# Adafruit_Feather_RP2040.net
KiCad netlist of a schematic drawn in EAGLE
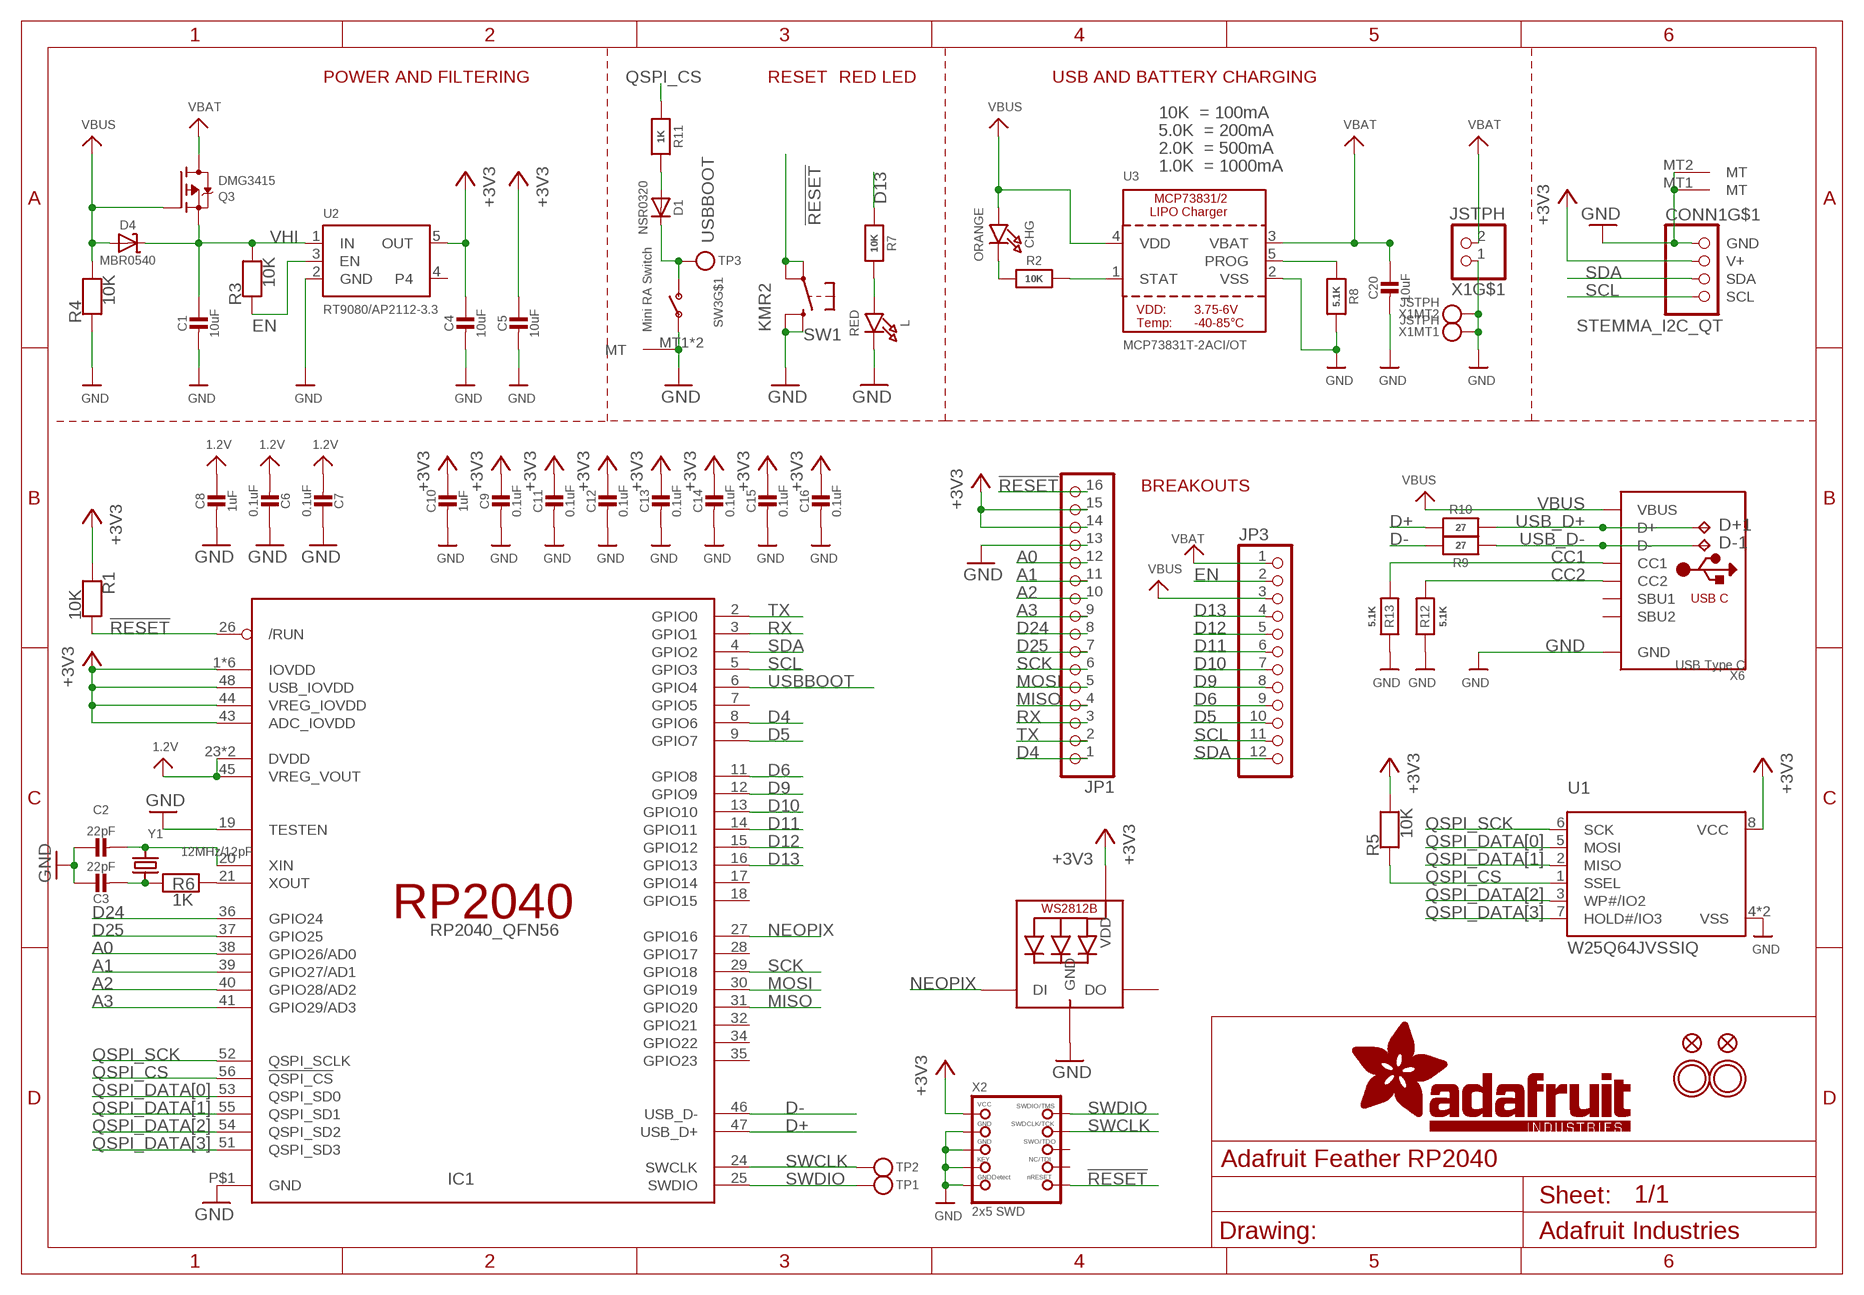
[diagram p0: schematic, sheet 1]

(export (version "E")
  (design (tool "Eeschema 10.0.6"))
  (components
    (comp (ref "C1")
      (value "10uF")
      (footprint "eagle-import:0805-NO")
      (libsource (lib "eagle-import") (part "CAP_CERAMIC0805-NOOUTLINE"))
    )
    (comp (ref "C2")
      (value "22pF")
      (footprint "eagle-import:0603-NO")
      (libsource (lib "eagle-import") (part "CAP_CERAMIC0603_NO"))
    )
    (comp (ref "C3")
      (value "22pF")
      (footprint "eagle-import:0603-NO")
      (libsource (lib "eagle-import") (part "CAP_CERAMIC0603_NO"))
    )
    (comp (ref "C4")
      (value "10uF")
      (footprint "eagle-import:0805-NO")
      (fields (field (name "REV") "D"))
      (libsource (lib "eagle-import") (part "CAP_CERAMIC0805-NOOUTLINE"))
    )
    (comp (ref "C5")
      (value "10uF")
      (footprint "eagle-import:0805-NO")
      (libsource (lib "eagle-import") (part "CAP_CERAMIC0805-NOOUTLINE"))
    )
    (comp (ref "C6")
      (value "0.1uF")
      (footprint "eagle-import:0603-NO")
      (libsource (lib "eagle-import") (part "CAP_CERAMIC0603_NO"))
    )
    (comp (ref "C7")
      (value "0.1uF")
      (footprint "eagle-import:0603-NO")
      (libsource (lib "eagle-import") (part "CAP_CERAMIC0603_NO"))
    )
    (comp (ref "C8")
      (value "1uF")
      (footprint "eagle-import:0603-NO")
      (libsource (lib "eagle-import") (part "CAP_CERAMIC0603_NO"))
    )
    (comp (ref "C9")
      (value "0.1uF")
      (footprint "eagle-import:0603-NO")
      (libsource (lib "eagle-import") (part "CAP_CERAMIC0603_NO"))
    )
    (comp (ref "C10")
      (value "1uF")
      (footprint "eagle-import:0603-NO")
      (libsource (lib "eagle-import") (part "CAP_CERAMIC0603_NO"))
    )
    (comp (ref "C11")
      (value "0.1uF")
      (footprint "eagle-import:0603-NO")
      (libsource (lib "eagle-import") (part "CAP_CERAMIC0603_NO"))
    )
    (comp (ref "C12")
      (value "0.1uF")
      (footprint "eagle-import:0603-NO")
      (libsource (lib "eagle-import") (part "CAP_CERAMIC0603_NO"))
    )
    (comp (ref "C13")
      (value "0.1uF")
      (footprint "eagle-import:0603-NO")
      (libsource (lib "eagle-import") (part "CAP_CERAMIC0603_NO"))
    )
    (comp (ref "C14")
      (value "0.1uF")
      (footprint "eagle-import:0603-NO")
      (libsource (lib "eagle-import") (part "CAP_CERAMIC0603_NO"))
    )
    (comp (ref "C15")
      (value "0.1uF")
      (footprint "eagle-import:0603-NO")
      (libsource (lib "eagle-import") (part "CAP_CERAMIC0603_NO"))
    )
    (comp (ref "C16")
      (value "0.1uF")
      (footprint "eagle-import:0603-NO")
      (libsource (lib "eagle-import") (part "CAP_CERAMIC0603_NO"))
    )
    (comp (ref "C20")
      (value "10uF")
      (footprint "eagle-import:0805-NO")
      (libsource (lib "eagle-import") (part "CAP_CERAMIC0805-NOOUTLINE"))
    )
    (comp (ref "CHG")
      (value "ORANGE")
      (footprint "eagle-import:CHIPLED_0603_NOOUTLINE")
      (libsource (lib "eagle-import") (part "LED0603_NOOUTLINE"))
    )
    (comp (ref "CONN1")
      (value "STEMMA_I2C_QT")
      (footprint "eagle-import:JST_SH4")
      (libsource (lib "eagle-import") (part "STEMMA_I2C_QT"))
    )
    (comp (ref "D+1")
      (value "TPB1,27")
      (footprint "eagle-import:B1,27")
      (libsource (lib "eagle-import") (part "TPB1,27"))
    )
    (comp (ref "D-1")
      (value "TPB1,27")
      (footprint "eagle-import:B1,27")
      (libsource (lib "eagle-import") (part "TPB1,27"))
    )
    (comp (ref "D1")
      (value "NSR0320")
      (footprint "eagle-import:SOD-323_MINI")
      (libsource (lib "eagle-import") (part "DIODE_SOD323MINI"))
    )
    (comp (ref "D4")
      (value "MBR0540")
      (footprint "eagle-import:SOD-123")
      (libsource (lib "eagle-import") (part "DIODE-SCHOTTKYSOD-123"))
    )
    (comp (ref "IC1")
      (value "RP2040_QFN56")
      (footprint "eagle-import:QFN56_7MM_REDUCEDEPAD")
      (libsource (lib "eagle-import") (part "RP2040_QFN56"))
    )
    (comp (ref "JP1")
      (value "HEADER-1X16ROUND")
      (footprint "eagle-import:1X16_ROUND")
      (libsource (lib "eagle-import") (part "HEADER-1X16ROUND"))
    )
    (comp (ref "JP3")
      (value "HEADER-1X12")
      (footprint "eagle-import:1X12_ROUND")
      (libsource (lib "eagle-import") (part "HEADER-1X12"))
    )
    (comp (ref "L")
      (value "RED")
      (footprint "eagle-import:CHIPLED_0603_NOOUTLINE")
      (libsource (lib "eagle-import") (part "LED0603_NOOUTLINE"))
    )
    (comp (ref "LED1")
      (value "WS2812B3535")
      (footprint "eagle-import:LED3535")
      (libsource (lib "eagle-import") (part "WS2812B3535"))
    )
    (comp (ref "Q3")
      (value "DMG3415")
      (footprint "eagle-import:SOT23-R")
      (libsource (lib "eagle-import") (part "MOSFET-P"))
    )
    (comp (ref "R1")
      (value "10K")
      (footprint "eagle-import:0603-NO")
      (libsource (lib "eagle-import") (part "RESISTOR_0603_NOOUT"))
    )
    (comp (ref "R2")
      (value "10K")
      (footprint "eagle-import:0603-NO")
      (libsource (lib "eagle-import") (part "RESISTOR_0603_NOOUT"))
    )
    (comp (ref "R3")
      (value "10K")
      (footprint "eagle-import:0603-NO")
      (libsource (lib "eagle-import") (part "RESISTOR_0603_NOOUT"))
    )
    (comp (ref "R4")
      (value "10K")
      (footprint "eagle-import:0603-NO")
      (libsource (lib "eagle-import") (part "RESISTOR_0603_NOOUT"))
    )
    (comp (ref "R5")
      (value "10K")
      (footprint "eagle-import:0603-NO")
      (libsource (lib "eagle-import") (part "RESISTOR_0603_NOOUT"))
    )
    (comp (ref "R6")
      (value "1K")
      (footprint "eagle-import:0603-NO")
      (libsource (lib "eagle-import") (part "RESISTOR_0603_NOOUT"))
    )
    (comp (ref "R7")
      (value "10K")
      (footprint "eagle-import:0603-NO")
      (libsource (lib "eagle-import") (part "RESISTOR_0603_NOOUT"))
    )
    (comp (ref "R8")
      (value "5.1K")
      (footprint "eagle-import:0603-NO")
      (libsource (lib "eagle-import") (part "RESISTOR_0603_NOOUT"))
    )
    (comp (ref "R9")
      (value "27")
      (footprint "eagle-import:0603-NO")
      (libsource (lib "eagle-import") (part "RESISTOR_0603_NOOUT"))
    )
    (comp (ref "R10")
      (value "27")
      (footprint "eagle-import:0603-NO")
      (libsource (lib "eagle-import") (part "RESISTOR_0603_NOOUT"))
    )
    (comp (ref "R11")
      (value "1K")
      (footprint "eagle-import:0603-NO")
      (libsource (lib "eagle-import") (part "RESISTOR_0603_NOOUT"))
    )
    (comp (ref "R12")
      (value "5.1K")
      (footprint "eagle-import:0603-NO")
      (libsource (lib "eagle-import") (part "RESISTOR_0603_NOOUT"))
    )
    (comp (ref "R13")
      (value "5.1K")
      (footprint "eagle-import:0603-NO")
      (libsource (lib "eagle-import") (part "RESISTOR_0603_NOOUT"))
    )
    (comp (ref "SW1")
      (value "KMR2")
      (footprint "eagle-import:BTN_KMR2_4.6X2.8")
      (libsource (lib "eagle-import") (part "SWITCH_TACT_SMT4.6X2.8"))
    )
    (comp (ref "SW3")
      (value "Mini RA Switch")
      (footprint "eagle-import:SPST_TACTILE_RA_2_4_3.5MM")
      (libsource (lib "eagle-import") (part "SWITCH_SPST_MNT_243.5"))
    )
    (comp (ref "TP1")
      (value "TESTPOINTROUND1.5MMNO")
      (footprint "eagle-import:TESTPOINT_ROUND_1.5MM_NO")
      (libsource (lib "eagle-import") (part "TESTPOINTROUND1.5MMNO"))
    )
    (comp (ref "TP2")
      (value "TESTPOINTROUND1.5MMNO")
      (footprint "eagle-import:TESTPOINT_ROUND_1.5MM_NO")
      (libsource (lib "eagle-import") (part "TESTPOINTROUND1.5MMNO"))
    )
    (comp (ref "TP3")
      (value "TESTPOINTROUND1.5MMNO")
      (footprint "eagle-import:TESTPOINT_ROUND_1.5MM_NO")
      (libsource (lib "eagle-import") (part "TESTPOINTROUND1.5MMNO"))
    )
    (comp (ref "U$31")
      (value "MOUNTINGHOLE2.5")
      (footprint "eagle-import:MOUNTINGHOLE_2.5_PLATED")
      (libsource (lib "eagle-import") (part "MOUNTINGHOLE2.5"))
    )
    (comp (ref "U$32")
      (value "MOUNTINGHOLE2.5")
      (footprint "eagle-import:MOUNTINGHOLE_2.5_PLATED")
      (libsource (lib "eagle-import") (part "MOUNTINGHOLE2.5"))
    )
    (comp (ref "U$34")
      (value "FIDUCIAL_1MM")
      (footprint "eagle-import:FIDUCIAL_1MM")
      (libsource (lib "eagle-import") (part "FIDUCIAL_1MM"))
    )
    (comp (ref "U$35")
      (value "FIDUCIAL_1MM")
      (footprint "eagle-import:FIDUCIAL_1MM")
      (libsource (lib "eagle-import") (part "FIDUCIAL_1MM"))
    )
    (comp (ref "U1")
      (value "W25Q64JVSSIQ")
      (footprint "eagle-import:USON8_4X4")
      (libsource (lib "eagle-import") (part "SPIFLASH_8PIN_4X4"))
    )
    (comp (ref "U2")
      (value "RT9080/AP2112-3.3")
      (footprint "eagle-import:SOT23-5")
      (fields (field (name "JLC_ROTATION") "0"))
      (libsource (lib "eagle-import") (part "VREG_SOT23-5"))
    )
    (comp (ref "U3")
      (value "MCP73831T-2ACI/OT")
      (footprint "eagle-import:SOT23-5")
      (libsource (lib "eagle-import") (part "MCP73831/2"))
    )
    (comp (ref "X1")
      (value "JSTPH")
      (footprint "eagle-import:JSTPH2_BATT")
      (libsource (lib "eagle-import") (part "CON_JST_PH_2PIN_MT_BATT"))
    )
    (comp (ref "X2")
      (value "2x5 SWD")
      (footprint "eagle-import:2X05_1.27MM_BOX_NOCREAM")
      (libsource (lib "eagle-import") (part "JTAG-CORTEX_NOCREAM"))
    )
    (comp (ref "X6")
      (value "USB Type C")
      (footprint "eagle-import:USB_C_CUSB31-CFM2AX-01-X")
      (libsource (lib "eagle-import") (part "USB_C"))
    )
    (comp (ref "Y1")
      (value "12MHz/12pF")
      (footprint "eagle-import:CRYSTAL_2.5X2")
      (libsource (lib "eagle-import") (part "CRYSTAL2.5X2.0"))
    )
  )
  (nets
    (net (code "1") (name "+3V3") (class "Default")
      (node (ref "C10") (pin "1") (pinfunction "1_1") (pintype "passive"))
      (node (ref "C11") (pin "1") (pinfunction "1_1") (pintype "passive"))
      (node (ref "C12") (pin "1") (pinfunction "1_1") (pintype "passive"))
      (node (ref "C13") (pin "1") (pinfunction "1_1") (pintype "passive"))
      (node (ref "C14") (pin "1") (pinfunction "1_1") (pintype "passive"))
      (node (ref "C15") (pin "1") (pinfunction "1_1") (pintype "passive"))
      (node (ref "C16") (pin "1") (pinfunction "1_1") (pintype "passive"))
      (node (ref "C4") (pin "1") (pinfunction "1_1") (pintype "passive"))
      (node (ref "C5") (pin "1") (pinfunction "1_1") (pintype "passive"))
      (node (ref "C9") (pin "1") (pinfunction "1_1") (pintype "passive"))
      (node (ref "CONN1") (pin "2") (pinfunction "V+_2") (pintype "passive"))
      (node (ref "IC1") (pin "1") (pinfunction "IOVDD_1") (pintype "power_in"))
      (node (ref "IC1") (pin "10") (pinfunction "IOVDD_10") (pintype "power_in"))
      (node (ref "IC1") (pin "22") (pinfunction "IOVDD_22") (pintype "power_in"))
      (node (ref "IC1") (pin "33") (pinfunction "IOVDD_33") (pintype "power_in"))
      (node (ref "IC1") (pin "42") (pinfunction "IOVDD_42") (pintype "power_in"))
      (node (ref "IC1") (pin "43") (pinfunction "ADC_IOVDD_43") (pintype "power_in"))
      (node (ref "IC1") (pin "44") (pinfunction "VREG_IOVDD_44") (pintype "power_in"))
      (node (ref "IC1") (pin "48") (pinfunction "USB_IOVDD_48") (pintype "power_in"))
      (node (ref "IC1") (pin "49") (pinfunction "IOVDD_49") (pintype "power_in"))
      (node (ref "JP1") (pin "14") (pinfunction "14_14") (pintype "passive"))
      (node (ref "JP1") (pin "15") (pinfunction "15_15") (pintype "passive"))
      (node (ref "LED1") (pin "2") (pinfunction "VDD_2") (pintype "power_in"))
      (node (ref "R1") (pin "1") (pinfunction "1_1") (pintype "passive"))
      (node (ref "R5") (pin "2") (pinfunction "2_2") (pintype "passive"))
      (node (ref "U1") (pin "8") (pinfunction "VCC_8") (pintype "bidirectional"))
      (node (ref "U2") (pin "5") (pinfunction "OUT_5") (pintype "power_in"))
      (node (ref "X2") (pin "1") (pinfunction "VCC_1") (pintype "power_in"))
    )
    (net (code "2") (name "/A0") (class "Default")
      (node (ref "IC1") (pin "38") (pinfunction "GPIO26/AD0_38") (pintype "bidirectional"))
      (node (ref "JP1") (pin "12") (pinfunction "12_12") (pintype "passive"))
    )
    (net (code "3") (name "/A1") (class "Default")
      (node (ref "IC1") (pin "39") (pinfunction "GPIO27/AD1_39") (pintype "bidirectional"))
      (node (ref "JP1") (pin "11") (pinfunction "11_11") (pintype "passive"))
    )
    (net (code "4") (name "/A2") (class "Default")
      (node (ref "IC1") (pin "40") (pinfunction "GPIO28/AD2_40") (pintype "bidirectional"))
      (node (ref "JP1") (pin "10") (pinfunction "10_10") (pintype "passive"))
    )
    (net (code "5") (name "/A3") (class "Default")
      (node (ref "IC1") (pin "41") (pinfunction "GPIO29/AD3_41") (pintype "bidirectional"))
      (node (ref "JP1") (pin "9") (pinfunction "9_9") (pintype "passive"))
    )
    (net (code "6") (name "/CC1") (class "Default")
      (node (ref "R13") (pin "2") (pinfunction "2_2") (pintype "passive"))
      (node (ref "X6") (pin "A5") (pinfunction "CC1_A5") (pintype "bidirectional"))
    )
    (net (code "7") (name "/CC2") (class "Default")
      (node (ref "R12") (pin "2") (pinfunction "2_2") (pintype "passive"))
      (node (ref "X6") (pin "B5") (pinfunction "CC2_B5") (pintype "bidirectional"))
    )
    (net (code "8") (name "/D+") (class "Default")
      (node (ref "IC1") (pin "47") (pinfunction "USB_D+_47") (pintype "bidirectional"))
      (node (ref "R10") (pin "2") (pinfunction "2_2") (pintype "passive"))
    )
    (net (code "9") (name "/D-") (class "Default")
      (node (ref "IC1") (pin "46") (pinfunction "USB_D-_46") (pintype "bidirectional"))
      (node (ref "R9") (pin "2") (pinfunction "2_2") (pintype "passive"))
    )
    (net (code "10") (name "/D4") (class "Default")
      (node (ref "IC1") (pin "8") (pinfunction "GPIO6_8") (pintype "bidirectional"))
      (node (ref "JP1") (pin "1") (pinfunction "1_1") (pintype "passive"))
    )
    (net (code "11") (name "/D5") (class "Default")
      (node (ref "IC1") (pin "9") (pinfunction "GPIO7_9") (pintype "bidirectional"))
      (node (ref "JP3") (pin "10") (pinfunction "10_10") (pintype "passive"))
    )
    (net (code "12") (name "/D6") (class "Default")
      (node (ref "IC1") (pin "11") (pinfunction "GPIO8_11") (pintype "bidirectional"))
      (node (ref "JP3") (pin "9") (pinfunction "9_9") (pintype "passive"))
    )
    (net (code "13") (name "/D9") (class "Default")
      (node (ref "IC1") (pin "12") (pinfunction "GPIO9_12") (pintype "bidirectional"))
      (node (ref "JP3") (pin "8") (pinfunction "8_8") (pintype "passive"))
    )
    (net (code "14") (name "/D10") (class "Default")
      (node (ref "IC1") (pin "13") (pinfunction "GPIO10_13") (pintype "bidirectional"))
      (node (ref "JP3") (pin "7") (pinfunction "7_7") (pintype "passive"))
    )
    (net (code "15") (name "/D11") (class "Default")
      (node (ref "IC1") (pin "14") (pinfunction "GPIO11_14") (pintype "bidirectional"))
      (node (ref "JP3") (pin "6") (pinfunction "6_6") (pintype "passive"))
    )
    (net (code "16") (name "/D12") (class "Default")
      (node (ref "IC1") (pin "15") (pinfunction "GPIO12_15") (pintype "bidirectional"))
      (node (ref "JP3") (pin "5") (pinfunction "5_5") (pintype "passive"))
    )
    (net (code "17") (name "/D13") (class "Default")
      (node (ref "IC1") (pin "16") (pinfunction "GPIO13_16") (pintype "bidirectional"))
      (node (ref "JP3") (pin "4") (pinfunction "4_4") (pintype "passive"))
      (node (ref "R7") (pin "1") (pinfunction "1_1") (pintype "passive"))
    )
    (net (code "18") (name "/D24") (class "Default")
      (node (ref "IC1") (pin "36") (pinfunction "GPIO24_36") (pintype "bidirectional"))
      (node (ref "JP1") (pin "8") (pinfunction "8_8") (pintype "passive"))
    )
    (net (code "19") (name "/D25") (class "Default")
      (node (ref "IC1") (pin "37") (pinfunction "GPIO25_37") (pintype "bidirectional"))
      (node (ref "JP1") (pin "7") (pinfunction "7_7") (pintype "passive"))
    )
    (net (code "20") (name "/EN") (class "Default")
      (node (ref "JP3") (pin "2") (pinfunction "2_2") (pintype "passive"))
      (node (ref "R3") (pin "1") (pinfunction "1_1") (pintype "passive"))
      (node (ref "U2") (pin "3") (pinfunction "EN_3") (pintype "input"))
    )
    (net (code "21") (name "/MISO") (class "Default")
      (node (ref "IC1") (pin "31") (pinfunction "GPIO20_31") (pintype "bidirectional"))
      (node (ref "JP1") (pin "4") (pinfunction "4_4") (pintype "passive"))
    )
    (net (code "22") (name "/MOSI") (class "Default")
      (node (ref "IC1") (pin "30") (pinfunction "GPIO19_30") (pintype "bidirectional"))
      (node (ref "JP1") (pin "5") (pinfunction "5_5") (pintype "passive"))
    )
    (net (code "23") (name "/NEOPIX") (class "Default")
      (node (ref "IC1") (pin "27") (pinfunction "GPIO16_27") (pintype "bidirectional"))
      (node (ref "LED1") (pin "1") (pinfunction "DI_1") (pintype "input"))
    )
    (net (code "24") (name "/QSPI_CS") (class "Default")
      (node (ref "IC1") (pin "56") (pinfunction "~{QSPI_CS}_56") (pintype "bidirectional"))
      (node (ref "R11") (pin "1") (pinfunction "1_1") (pintype "passive"))
      (node (ref "R5") (pin "1") (pinfunction "1_1") (pintype "passive"))
      (node (ref "U1") (pin "1") (pinfunction "SSEL_1") (pintype "bidirectional"))
    )
    (net (code "25") (name "/QSPI_DATA[0]") (class "Default")
      (node (ref "IC1") (pin "53") (pinfunction "QSPI_SD0_53") (pintype "bidirectional"))
      (node (ref "U1") (pin "5") (pinfunction "MOSI_5") (pintype "bidirectional"))
    )
    (net (code "26") (name "/QSPI_DATA[1]") (class "Default")
      (node (ref "IC1") (pin "55") (pinfunction "QSPI_SD1_55") (pintype "bidirectional"))
      (node (ref "U1") (pin "2") (pinfunction "MISO_2") (pintype "bidirectional"))
    )
    (net (code "27") (name "/QSPI_DATA[2]") (class "Default")
      (node (ref "IC1") (pin "54") (pinfunction "QSPI_SD2_54") (pintype "bidirectional"))
      (node (ref "U1") (pin "3") (pinfunction "WP#/IO2_3") (pintype "bidirectional"))
    )
    (net (code "28") (name "/QSPI_DATA[3]") (class "Default")
      (node (ref "IC1") (pin "51") (pinfunction "QSPI_SD3_51") (pintype "bidirectional"))
      (node (ref "U1") (pin "7") (pinfunction "HOLD#/IO3_7") (pintype "bidirectional"))
    )
    (net (code "29") (name "/QSPI_SCK") (class "Default")
      (node (ref "IC1") (pin "52") (pinfunction "QSPI_SCLK_52") (pintype "bidirectional"))
      (node (ref "U1") (pin "6") (pinfunction "SCK_6") (pintype "bidirectional"))
    )
    (net (code "30") (name "/RX") (class "Default")
      (node (ref "IC1") (pin "3") (pinfunction "GPIO1_3") (pintype "bidirectional"))
      (node (ref "JP1") (pin "3") (pinfunction "3_3") (pintype "passive"))
    )
    (net (code "31") (name "/SCK") (class "Default")
      (node (ref "IC1") (pin "29") (pinfunction "GPIO18_29") (pintype "bidirectional"))
      (node (ref "JP1") (pin "6") (pinfunction "6_6") (pintype "passive"))
    )
    (net (code "32") (name "/SCL") (class "Default")
      (node (ref "CONN1") (pin "4") (pinfunction "SCL_4") (pintype "passive"))
      (node (ref "IC1") (pin "5") (pinfunction "GPIO3_5") (pintype "bidirectional"))
      (node (ref "JP3") (pin "11") (pinfunction "11_11") (pintype "passive"))
    )
    (net (code "33") (name "/SDA") (class "Default")
      (node (ref "CONN1") (pin "3") (pinfunction "SDA_3") (pintype "passive"))
      (node (ref "IC1") (pin "4") (pinfunction "GPIO2_4") (pintype "bidirectional"))
      (node (ref "JP3") (pin "12") (pinfunction "12_12") (pintype "passive"))
    )
    (net (code "34") (name "/SWCLK") (class "Default")
      (node (ref "IC1") (pin "24") (pinfunction "SWCLK_24") (pintype "bidirectional"))
      (node (ref "TP2") (pin "P$1") (pinfunction "P$1_P$1") (pintype "bidirectional"))
      (node (ref "X2") (pin "4") (pinfunction "SWDCLK_4") (pintype "bidirectional"))
    )
    (net (code "35") (name "/SWDIO") (class "Default")
      (node (ref "IC1") (pin "25") (pinfunction "SWDIO_25") (pintype "bidirectional"))
      (node (ref "TP1") (pin "P$1") (pinfunction "P$1_P$1") (pintype "bidirectional"))
      (node (ref "X2") (pin "2") (pinfunction "SWDIO_2") (pintype "bidirectional"))
    )
    (net (code "36") (name "/TX") (class "Default")
      (node (ref "IC1") (pin "2") (pinfunction "GPIO0_2") (pintype "bidirectional"))
      (node (ref "JP1") (pin "2") (pinfunction "2_2") (pintype "passive"))
    )
    (net (code "37") (name "/USBBOOT") (class "Default")
      (node (ref "D1") (pin "C") (pinfunction "C_C") (pintype "passive"))
      (node (ref "IC1") (pin "6") (pinfunction "GPIO4_6") (pintype "bidirectional"))
      (node (ref "SW3") (pin "2") (pinfunction "S_2") (pintype "passive"))
      (node (ref "TP3") (pin "P$1") (pinfunction "P$1_P$1") (pintype "bidirectional"))
    )
    (net (code "38") (name "/USB_D+") (class "Default")
      (node (ref "D+1") (pin "TP") (pinfunction "TP_TP") (pintype "input"))
      (node (ref "R10") (pin "1") (pinfunction "1_1") (pintype "passive"))
      (node (ref "X6") (pin "A6") (pinfunction "D+_A6") (pintype "bidirectional"))
      (node (ref "X6") (pin "B6") (pinfunction "D+_B6") (pintype "bidirectional"))
    )
    (net (code "39") (name "/USB_D-") (class "Default")
      (node (ref "D-1") (pin "TP") (pinfunction "TP_TP") (pintype "input"))
      (node (ref "R9") (pin "1") (pinfunction "1_1") (pintype "passive"))
      (node (ref "X6") (pin "A7") (pinfunction "D-_A7") (pintype "bidirectional"))
      (node (ref "X6") (pin "B7") (pinfunction "D-_B7") (pintype "bidirectional"))
    )
    (net (code "40") (name "/VHI") (class "Default")
      (node (ref "C1") (pin "1") (pinfunction "1_1") (pintype "passive"))
      (node (ref "D4") (pin "C") (pinfunction "C_C") (pintype "passive"))
      (node (ref "Q3") (pin "2") (pinfunction "S_2") (pintype "passive"))
      (node (ref "R3") (pin "2") (pinfunction "2_2") (pintype "passive"))
      (node (ref "U2") (pin "1") (pinfunction "IN_1") (pintype "power_in"))
    )
    (net (code "41") (name "/~{RESET}") (class "Default")
      (node (ref "IC1") (pin "26") (pinfunction "/RUN_26") (pintype "bidirectional"))
      (node (ref "JP1") (pin "16") (pinfunction "16_16") (pintype "passive"))
      (node (ref "R1") (pin "2") (pinfunction "2_2") (pintype "passive"))
      (node (ref "SW1") (pin "A") (pinfunction "P_A") (pintype "passive"))
      (node (ref "SW1") (pin "A'") (pinfunction "P1_A'") (pintype "passive"))
      (node (ref "X2") (pin "10") (pinfunction "NRESET_10") (pintype "bidirectional"))
    )
    (net (code "42") (name "1.2V") (class "Default")
      (node (ref "C6") (pin "2") (pinfunction "2_2") (pintype "passive"))
      (node (ref "C7") (pin "2") (pinfunction "2_2") (pintype "passive"))
      (node (ref "C8") (pin "1") (pinfunction "1_1") (pintype "passive"))
      (node (ref "IC1") (pin "23") (pinfunction "DVDD_23") (pintype "power_in"))
      (node (ref "IC1") (pin "45") (pinfunction "VREG_VOUT_45") (pintype "power_in"))
      (node (ref "IC1") (pin "50") (pinfunction "DVDD_50") (pintype "power_in"))
    )
    (net (code "43") (name "GND") (class "Default")
      (node (ref "C1") (pin "2") (pinfunction "2_2") (pintype "passive"))
      (node (ref "C10") (pin "2") (pinfunction "2_2") (pintype "passive"))
      (node (ref "C11") (pin "2") (pinfunction "2_2") (pintype "passive"))
      (node (ref "C12") (pin "2") (pinfunction "2_2") (pintype "passive"))
      (node (ref "C13") (pin "2") (pinfunction "2_2") (pintype "passive"))
      (node (ref "C14") (pin "2") (pinfunction "2_2") (pintype "passive"))
      (node (ref "C15") (pin "2") (pinfunction "2_2") (pintype "passive"))
      (node (ref "C16") (pin "2") (pinfunction "2_2") (pintype "passive"))
      (node (ref "C2") (pin "1") (pinfunction "1_1") (pintype "passive"))
      (node (ref "C20") (pin "2") (pinfunction "2_2") (pintype "passive"))
      (node (ref "C3") (pin "1") (pinfunction "1_1") (pintype "passive"))
      (node (ref "C4") (pin "2") (pinfunction "2_2") (pintype "passive"))
      (node (ref "C5") (pin "2") (pinfunction "2_2") (pintype "passive"))
      (node (ref "C6") (pin "1") (pinfunction "1_1") (pintype "passive"))
      (node (ref "C7") (pin "1") (pinfunction "1_1") (pintype "passive"))
      (node (ref "C8") (pin "2") (pinfunction "2_2") (pintype "passive"))
      (node (ref "C9") (pin "2") (pinfunction "2_2") (pintype "passive"))
      (node (ref "CONN1") (pin "1") (pinfunction "GND_1") (pintype "passive"))
      (node (ref "CONN1") (pin "MT1") (pinfunction "MT_MT1") (pintype "bidirectional"))
      (node (ref "CONN1") (pin "MT2") (pinfunction "MT_MT2") (pintype "bidirectional"))
      (node (ref "IC1") (pin "19") (pinfunction "TESTEN_19") (pintype "input"))
      (node (ref "IC1") (pin "P$1") (pinfunction "GND_P$1") (pintype "power_in"))
      (node (ref "JP1") (pin "13") (pinfunction "13_13") (pintype "passive"))
      (node (ref "L") (pin "C") (pinfunction "C_C") (pintype "passive"))
      (node (ref "LED1") (pin "4") (pinfunction "GND_4") (pintype "power_in"))
      (node (ref "R12") (pin "1") (pinfunction "1_1") (pintype "passive"))
      (node (ref "R13") (pin "1") (pinfunction "1_1") (pintype "passive"))
      (node (ref "R4") (pin "1") (pinfunction "1_1") (pintype "passive"))
      (node (ref "R8") (pin "2") (pinfunction "2_2") (pintype "passive"))
      (node (ref "SW1") (pin "B") (pinfunction "S_B") (pintype "passive"))
      (node (ref "SW1") (pin "B'") (pinfunction "S1_B'") (pintype "passive"))
      (node (ref "SW3") (pin "1") (pinfunction "P_1") (pintype "passive"))
      (node (ref "SW3") (pin "MT1") (pinfunction "MT_MT1") (pintype "bidirectional"))
      (node (ref "SW3") (pin "MT2") (pinfunction "MT_MT2") (pintype "bidirectional"))
      (node (ref "U1") (pin "4") (pinfunction "VSS_4") (pintype "bidirectional"))
      (node (ref "U1") (pin "PAD") (pinfunction "VSS_PAD") (pintype "bidirectional"))
      (node (ref "U2") (pin "2") (pinfunction "GND_2") (pintype "power_in"))
      (node (ref "U3") (pin "2") (pinfunction "VSS_2") (pintype "power_in"))
      (node (ref "X1") (pin "1") (pinfunction "1_1") (pintype "passive"))
      (node (ref "X1") (pin "NC1") (pinfunction "P$1_NC1") (pintype "bidirectional"))
      (node (ref "X1") (pin "NC2") (pinfunction "P$1_NC2") (pintype "bidirectional"))
      (node (ref "X2") (pin "3") (pinfunction "GND_3") (pintype "power_in"))
      (node (ref "X2") (pin "5") (pinfunction "GND_5") (pintype "power_in"))
      (node (ref "X2") (pin "7") (pinfunction "KEY_7") (pintype "bidirectional"))
      (node (ref "X2") (pin "9") (pinfunction "GNDDETECT_9") (pintype "bidirectional"))
      (node (ref "X6") (pin "A1B12") (pinfunction "GND_A1B12") (pintype "power_in"))
      (node (ref "X6") (pin "B1A12") (pinfunction "GND_B1A12") (pintype "power_in"))
    )
    (net (code "44") (name "Net-(C3-Pad2)") (class "Default")
      (node (ref "C3") (pin "2") (pinfunction "2_2") (pintype "passive"))
      (node (ref "R6") (pin "1") (pinfunction "1_1") (pintype "passive"))
      (node (ref "Y1") (pin "1") (pinfunction "1_1") (pintype "passive"))
    )
    (net (code "45") (name "Net-(CHG-PadC)") (class "Default")
      (node (ref "CHG") (pin "C") (pinfunction "C_C") (pintype "passive"))
      (node (ref "R2") (pin "1") (pinfunction "1_1") (pintype "passive"))
    )
    (net (code "46") (name "Net-(D1-PadA)") (class "Default")
      (node (ref "D1") (pin "A") (pinfunction "A_A") (pintype "passive"))
      (node (ref "R11") (pin "2") (pinfunction "2_2") (pintype "passive"))
    )
    (net (code "47") (name "Net-(IC1-XIN)") (class "Default")
      (node (ref "C2") (pin "2") (pinfunction "2_2") (pintype "passive"))
      (node (ref "IC1") (pin "20") (pinfunction "XIN_20") (pintype "input"))
      (node (ref "Y1") (pin "3") (pinfunction "2_3") (pintype "passive"))
    )
    (net (code "48") (name "Net-(IC1-XOUT)") (class "Default")
      (node (ref "IC1") (pin "21") (pinfunction "XOUT_21") (pintype "output"))
      (node (ref "R6") (pin "2") (pinfunction "2_2") (pintype "passive"))
    )
    (net (code "49") (name "Net-(L-PadA)") (class "Default")
      (node (ref "L") (pin "A") (pinfunction "A_A") (pintype "passive"))
      (node (ref "R7") (pin "2") (pinfunction "2_2") (pintype "passive"))
    )
    (net (code "50") (name "Net-(U3-PROG)") (class "Default")
      (node (ref "R8") (pin "1") (pinfunction "1_1") (pintype "passive"))
      (node (ref "U3") (pin "5") (pinfunction "PROG_5") (pintype "input"))
    )
    (net (code "51") (name "Net-(U3-STAT)") (class "Default")
      (node (ref "R2") (pin "2") (pinfunction "2_2") (pintype "passive"))
      (node (ref "U3") (pin "1") (pinfunction "STAT_1") (pintype "output"))
    )
    (net (code "52") (name "VBAT") (class "Default")
      (node (ref "C20") (pin "1") (pinfunction "1_1") (pintype "passive"))
      (node (ref "JP3") (pin "1") (pinfunction "1_1") (pintype "passive"))
      (node (ref "Q3") (pin "3") (pinfunction "D_3") (pintype "passive"))
      (node (ref "U3") (pin "3") (pinfunction "VBAT_3") (pintype "power_in"))
      (node (ref "X1") (pin "2") (pinfunction "2_2") (pintype "passive"))
    )
    (net (code "53") (name "VBUS") (class "Default")
      (node (ref "CHG") (pin "A") (pinfunction "A_A") (pintype "passive"))
      (node (ref "D4") (pin "A") (pinfunction "A_A") (pintype "passive"))
      (node (ref "JP3") (pin "3") (pinfunction "3_3") (pintype "passive"))
      (node (ref "Q3") (pin "1") (pinfunction "G_1") (pintype "passive"))
      (node (ref "R4") (pin "2") (pinfunction "2_2") (pintype "passive"))
      (node (ref "U3") (pin "4") (pinfunction "VDD_4") (pintype "power_in"))
      (node (ref "X6") (pin "A4B9") (pinfunction "VBUS_A4B9") (pintype "power_in"))
      (node (ref "X6") (pin "B4A9") (pinfunction "VBUS_B4A9") (pintype "power_in"))
    )
    (net (code "54") (name "unconnected-(IC1-GPIO5-Pad7)") (class "Default")
      (node (ref "IC1") (pin "7") (pinfunction "GPIO5_7") (pintype "bidirectional"))
    )
    (net (code "55") (name "unconnected-(IC1-GPIO14-Pad17)") (class "Default")
      (node (ref "IC1") (pin "17") (pinfunction "GPIO14_17") (pintype "bidirectional"))
    )
    (net (code "56") (name "unconnected-(IC1-GPIO15-Pad18)") (class "Default")
      (node (ref "IC1") (pin "18") (pinfunction "GPIO15_18") (pintype "bidirectional"))
    )
    (net (code "57") (name "unconnected-(IC1-GPIO17-Pad28)") (class "Default")
      (node (ref "IC1") (pin "28") (pinfunction "GPIO17_28") (pintype "bidirectional"))
    )
    (net (code "58") (name "unconnected-(IC1-GPIO21-Pad32)") (class "Default")
      (node (ref "IC1") (pin "32") (pinfunction "GPIO21_32") (pintype "bidirectional"))
    )
    (net (code "59") (name "unconnected-(IC1-GPIO22-Pad34)") (class "Default")
      (node (ref "IC1") (pin "34") (pinfunction "GPIO22_34") (pintype "bidirectional"))
    )
    (net (code "60") (name "unconnected-(IC1-GPIO23-Pad35)") (class "Default")
      (node (ref "IC1") (pin "35") (pinfunction "GPIO23_35") (pintype "bidirectional"))
    )
    (net (code "61") (name "unconnected-(LED1-DO-Pad3)") (class "Default")
      (node (ref "LED1") (pin "3") (pinfunction "DO_3") (pintype "output"))
    )
    (net (code "62") (name "unconnected-(U2-P4-Pad4)") (class "Default")
      (node (ref "U2") (pin "4") (pinfunction "P4_4") (pintype "bidirectional"))
    )
    (net (code "63") (name "unconnected-(X2-SWO-Pad6)") (class "Default")
      (node (ref "X2") (pin "6") (pinfunction "SWO_6") (pintype "bidirectional"))
    )
    (net (code "64") (name "unconnected-(X2-TDI-Pad8)") (class "Default")
      (node (ref "X2") (pin "8") (pinfunction "TDI_8") (pintype "bidirectional"))
    )
    (net (code "65") (name "unconnected-(X6-SBU1-PadA8)") (class "Default")
      (node (ref "X6") (pin "A8") (pinfunction "SBU1_A8") (pintype "bidirectional"))
    )
    (net (code "66") (name "unconnected-(X6-SBU2-PadB8)") (class "Default")
      (node (ref "X6") (pin "B8") (pinfunction "SBU2_B8") (pintype "bidirectional"))
    )
  )
)
